# gps-breakout-mk-1_4.net
KiCad netlist of a schematic drawn in EAGLE
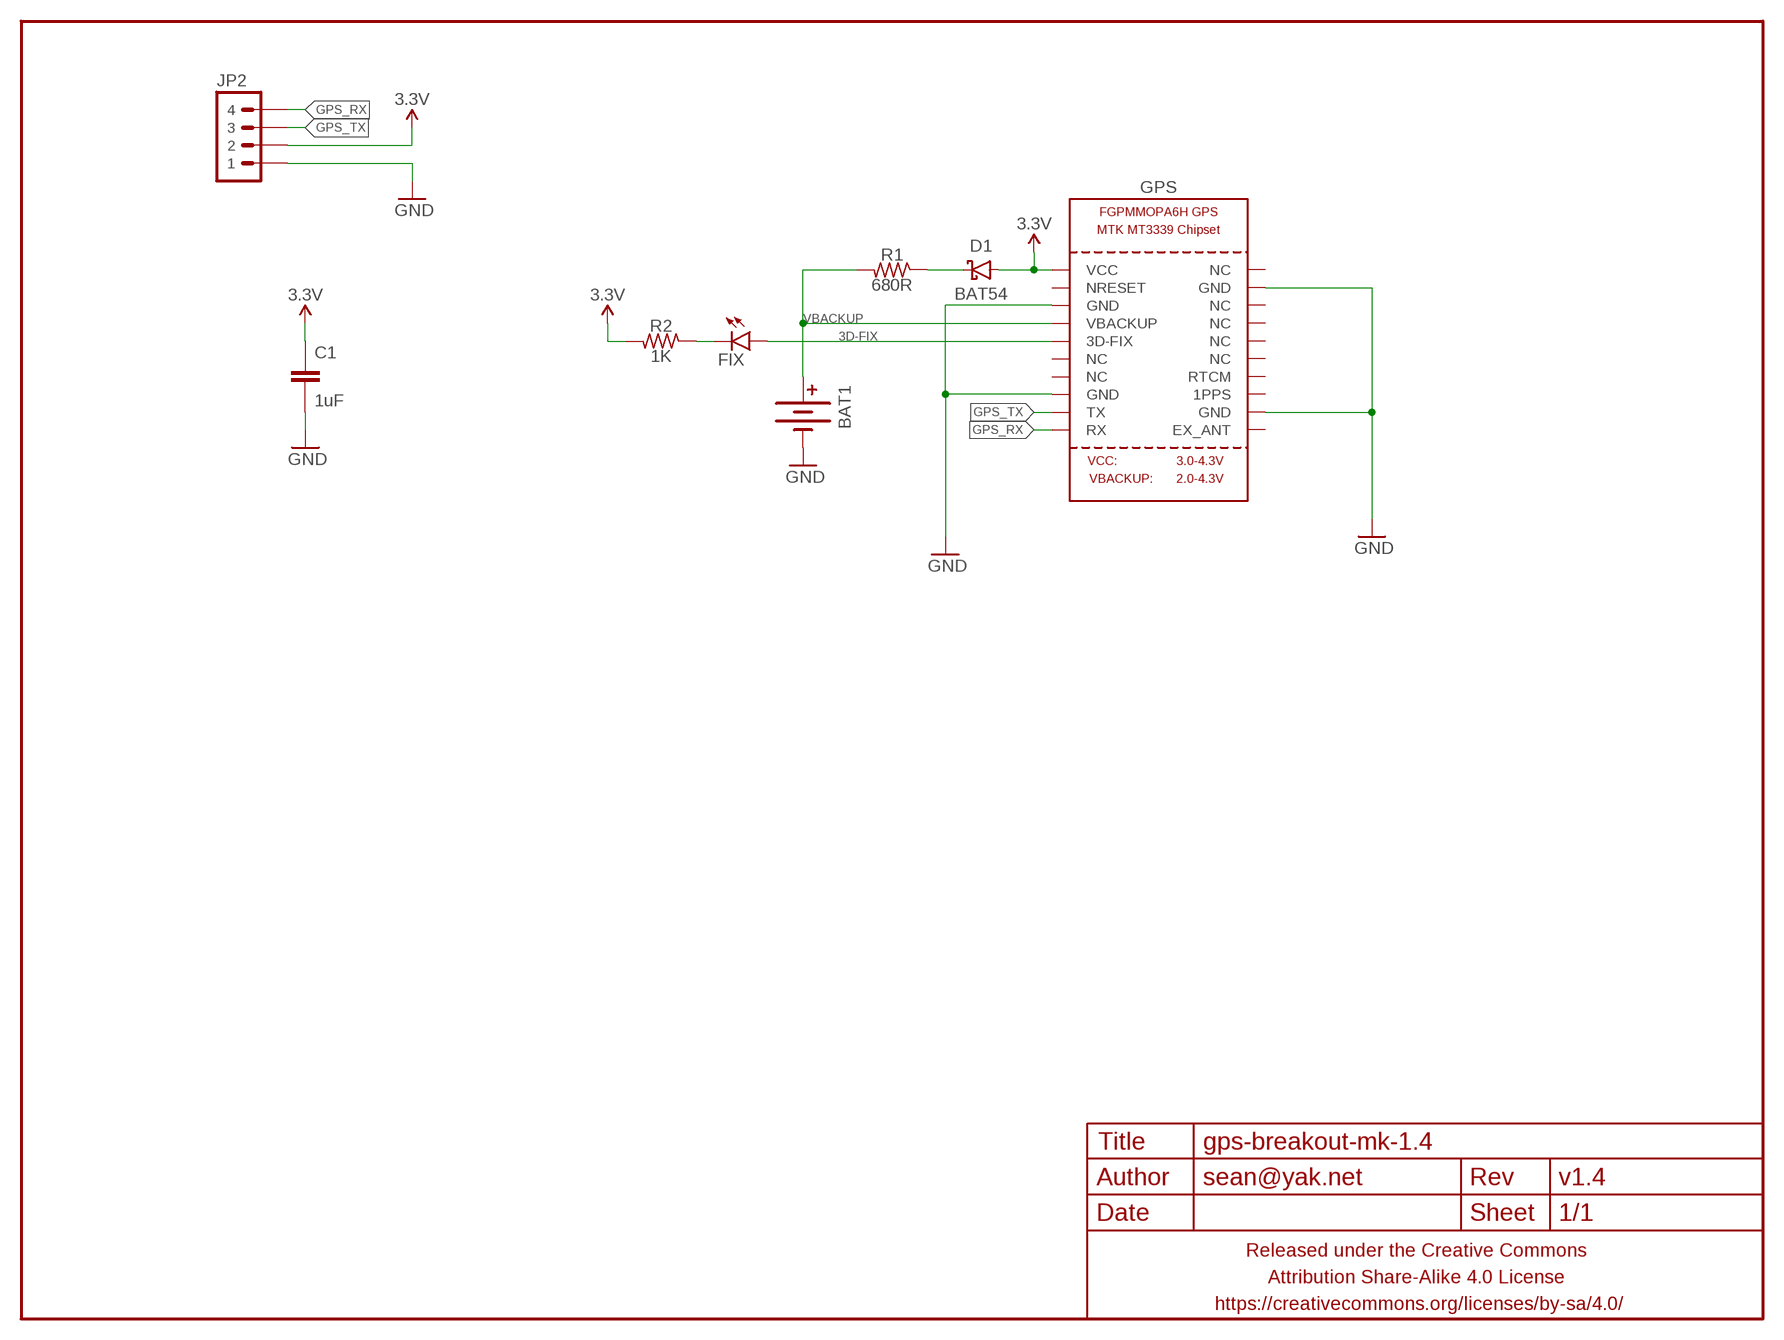
[diagram p0: schematic, sheet 1]

(export (version "E")
  (design (tool "Eeschema 10.0.6"))
  (components
    (comp (ref "BAT1")
      (value "BATTERYML414")
      (footprint "eagle-import:BATTCON_4.8MM")
      (libsource (lib "eagle-import") (part "BATTERYML414"))
    )
    (comp (ref "C1")
      (value "1uF")
      (footprint "eagle-import:C0603-TIGHTER")
      (libsource (lib "eagle-import") (part "CAPACITOR-CERAMICC0603-TIGHTER"))
    )
    (comp (ref "D1")
      (value "BAT54")
      (footprint "eagle-import:SOD323-SCHOTTKY")
      (libsource (lib "eagle-import") (part "DIODE-SCHOTTKYSOD323"))
    )
    (comp (ref "FIX")
      (value "LED0603-TIGHT")
      (footprint "eagle-import:LED-0603-TIGHT")
      (libsource (lib "eagle-import") (part "LED0603-TIGHT"))
    )
    (comp (ref "FRAME1")
      (value "FRAME-LETTERNO_PACKAGE")
      (footprint "eagle-import:DUMMY")
      (fields
        (field (name "DESIGNER") "Nobody")
        (field (name "VERSION") "v01")
        (field (name "DESIGNER_1") "sean@yak.net")
        (field (name "VERSION_1") "v1.4")
      )
      (libsource (lib "eagle-import") (part "FRAME-LETTERNO_PACKAGE"))
    )
    (comp (ref "GPS")
      (value "GPS_FGPMMOPA6H")
      (footprint "eagle-import:FGPMMOPA6H")
      (libsource (lib "eagle-import") (part "GPS_FGPMMOPA6H"))
    )
    (comp (ref "JP2")
      (value "M04SMD-FEMALE")
      (footprint "eagle-import:1X04-SMD-FEMALE-RA")
      (libsource (lib "eagle-import") (part "M04SMD-FEMALE"))
    )
    (comp (ref "R1")
      (value "680R")
      (footprint "eagle-import:R0603-TIGHTER")
      (libsource (lib "eagle-import") (part "RESISTORR0603-TIGHTER"))
    )
    (comp (ref "R2")
      (value "1K")
      (footprint "eagle-import:R0603-TIGHTER")
      (libsource (lib "eagle-import") (part "RESISTORR0603-TIGHTER"))
    )
  )
  (nets
    (net (code "1") (name "/3D-FIX") (class "Default")
      (node (ref "FIX") (pin "A") (pinfunction "A_A") (pintype "passive"))
      (node (ref "GPS") (pin "P$5") (pinfunction "3D-FIX_P$5") (pintype "bidirectional"))
    )
    (net (code "2") (name "/VBACKUP") (class "Default")
      (node (ref "BAT1") (pin "A1") (pinfunction "+_A1") (pintype "power_in"))
      (node (ref "BAT1") (pin "A2") (pinfunction "+_A2") (pintype "power_in"))
      (node (ref "GPS") (pin "P$4") (pinfunction "VBACKUP_P$4") (pintype "bidirectional"))
      (node (ref "R1") (pin "2") (pinfunction "2_2") (pintype "passive"))
    )
    (net (code "3") (name "3.3V") (class "Default")
      (node (ref "C1") (pin "1") (pinfunction "1_1") (pintype "passive"))
      (node (ref "D1") (pin "A") (pinfunction "A_A") (pintype "passive"))
      (node (ref "GPS") (pin "P$1") (pinfunction "VCC_P$1") (pintype "bidirectional"))
      (node (ref "JP2") (pin "P$2") (pinfunction "2_P$2") (pintype "passive"))
      (node (ref "R2") (pin "2") (pinfunction "2_2") (pintype "passive"))
    )
    (net (code "4") (name "GND") (class "Default")
      (node (ref "BAT1") (pin "-") (pinfunction "-_-") (pintype "power_in"))
      (node (ref "C1") (pin "2") (pinfunction "2_2") (pintype "passive"))
      (node (ref "GPS") (pin "P$12") (pinfunction "GND_P$12") (pintype "bidirectional"))
      (node (ref "GPS") (pin "P$19") (pinfunction "GND_P$19") (pintype "bidirectional"))
      (node (ref "GPS") (pin "P$3") (pinfunction "GND_P$3") (pintype "bidirectional"))
      (node (ref "GPS") (pin "P$8") (pinfunction "GND_P$8") (pintype "bidirectional"))
      (node (ref "JP2") (pin "P$1") (pinfunction "1_P$1") (pintype "passive"))
    )
    (net (code "5") (name "GPS_RX") (class "Default")
      (node (ref "GPS") (pin "P$10") (pinfunction "RX_P$10") (pintype "bidirectional"))
      (node (ref "JP2") (pin "P$4") (pinfunction "4_P$4") (pintype "passive"))
    )
    (net (code "6") (name "GPS_TX") (class "Default")
      (node (ref "GPS") (pin "P$9") (pinfunction "TX_P$9") (pintype "bidirectional"))
      (node (ref "JP2") (pin "P$3") (pinfunction "3_P$3") (pintype "passive"))
    )
    (net (code "7") (name "Net-(D1-PadC)") (class "Default")
      (node (ref "D1") (pin "C") (pinfunction "C_C") (pintype "passive"))
      (node (ref "R1") (pin "1") (pinfunction "1_1") (pintype "passive"))
    )
    (net (code "8") (name "Net-(FIX-PadC)") (class "Default")
      (node (ref "FIX") (pin "C") (pinfunction "C_C") (pintype "passive"))
      (node (ref "R2") (pin "1") (pinfunction "1_1") (pintype "passive"))
    )
    (net (code "9") (name "unconnected-(GPS-1PPS-PadP$13)") (class "Default")
      (node (ref "GPS") (pin "P$13") (pinfunction "1PPS_P$13") (pintype "bidirectional"))
    )
    (net (code "10") (name "unconnected-(GPS-EX_ANT-PadP$11)") (class "Default")
      (node (ref "GPS") (pin "P$11") (pinfunction "EX_ANT_P$11") (pintype "bidirectional"))
    )
    (net (code "11") (name "unconnected-(GPS-NC-PadP$6)") (class "Default")
      (node (ref "GPS") (pin "P$6") (pinfunction "NC_P$6") (pintype "bidirectional"))
    )
    (net (code "12") (name "unconnected-(GPS-NC-PadP$7)") (class "Default")
      (node (ref "GPS") (pin "P$7") (pinfunction "NC_P$7") (pintype "bidirectional"))
    )
    (net (code "13") (name "unconnected-(GPS-NC-PadP$15)") (class "Default")
      (node (ref "GPS") (pin "P$15") (pinfunction "NC_P$15") (pintype "bidirectional"))
    )
    (net (code "14") (name "unconnected-(GPS-NC-PadP$16)") (class "Default")
      (node (ref "GPS") (pin "P$16") (pinfunction "NC_P$16") (pintype "bidirectional"))
    )
    (net (code "15") (name "unconnected-(GPS-NC-PadP$17)") (class "Default")
      (node (ref "GPS") (pin "P$17") (pinfunction "NC_P$17") (pintype "bidirectional"))
    )
    (net (code "16") (name "unconnected-(GPS-NC-PadP$18)") (class "Default")
      (node (ref "GPS") (pin "P$18") (pinfunction "NC_P$18") (pintype "bidirectional"))
    )
    (net (code "17") (name "unconnected-(GPS-NC-PadP$20)") (class "Default")
      (node (ref "GPS") (pin "P$20") (pinfunction "NC_P$20") (pintype "bidirectional"))
    )
    (net (code "18") (name "unconnected-(GPS-NRESET-PadP$2)") (class "Default")
      (node (ref "GPS") (pin "P$2") (pinfunction "NRESET_P$2") (pintype "bidirectional"))
    )
    (net (code "19") (name "unconnected-(GPS-RTCM-PadP$14)") (class "Default")
      (node (ref "GPS") (pin "P$14") (pinfunction "RTCM_P$14") (pintype "bidirectional"))
    )
  )
)
